# Session_4_HW.net
KiCad netlist of a schematic drawn in EAGLE
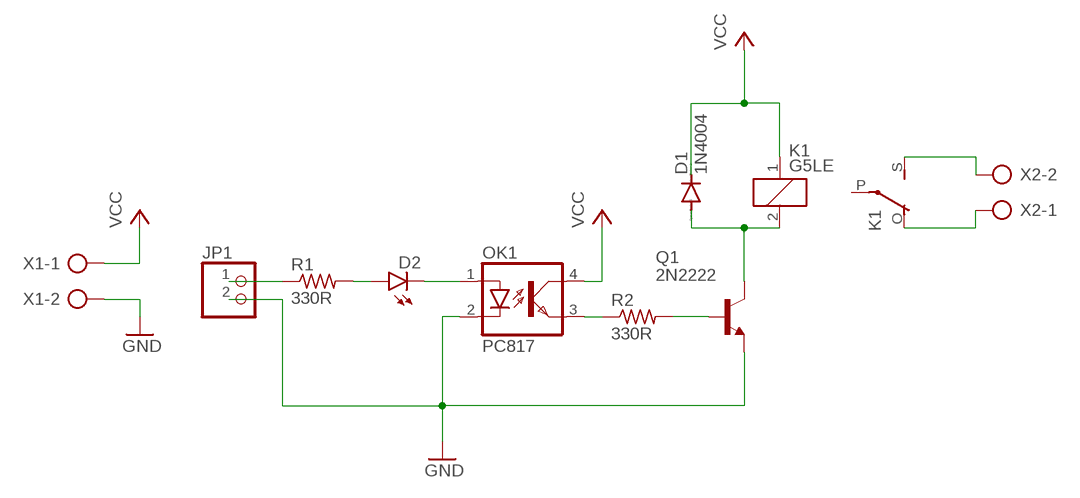
[diagram p0: schematic, sheet 1]

(export (version "E")
  (design (tool "Eeschema 10.0.6"))
  (components
    (comp (ref "D1")
      (value "1N4004")
      (footprint "eagle-import:DO41-10")
      (libsource (lib "eagle-import") (part "1N4004"))
    )
    (comp (ref "D2")
      (value "LED5MM")
      (footprint "eagle-import:LED5MM")
      (libsource (lib "eagle-import") (part "LED5MM"))
    )
    (comp (ref "JP1")
      (value "PINHD-1X2")
      (footprint "eagle-import:1X02")
      (libsource (lib "eagle-import") (part "PINHD-1X2"))
    )
    (comp (ref "K1")
      (value "G5LE")
      (footprint "eagle-import:G5LE")
      (libsource (lib "eagle-import") (part "G5LE"))
    )
    (comp (ref "OK1")
      (value "PC817")
      (footprint "eagle-import:DIL04")
      (fields (field (name "MPN") "PC817X4J000F"))
      (libsource (lib "eagle-import") (part "PC817"))
    )
    (comp (ref "Q1")
      (value "2N2222")
      (footprint "eagle-import:TO18")
      (libsource (lib "eagle-import") (part "2N2222"))
    )
    (comp (ref "R1")
      (value "330R")
      (footprint "eagle-import:0204_7")
      (libsource (lib "eagle-import") (part "R-US_0204/7"))
    )
    (comp (ref "R2")
      (value "330R")
      (footprint "eagle-import:0204_7")
      (libsource (lib "eagle-import") (part "R-US_0204/7"))
    )
    (comp (ref "X1")
      (value "AK500/2")
      (footprint "eagle-import:AK500_2")
      (libsource (lib "eagle-import") (part "AK500/2"))
    )
    (comp (ref "X2")
      (value "AK500/2")
      (footprint "eagle-import:AK500_2")
      (libsource (lib "eagle-import") (part "AK500/2"))
    )
  )
  (nets
    (net (code "1") (name "GND") (class "Default")
      (node (ref "JP1") (pin "2") (pinfunction "2_2") (pintype "passive"))
      (node (ref "OK1") (pin "2") (pinfunction "C_2") (pintype "passive"))
      (node (ref "Q1") (pin "1") (pinfunction "E_1") (pintype "passive"))
      (node (ref "X1") (pin "2") (pinfunction "KL_2") (pintype "passive"))
    )
    (net (code "2") (name "Net-(D2-C)") (class "Default")
      (node (ref "D2") (pin "K") (pinfunction "C_K") (pintype "passive"))
      (node (ref "OK1") (pin "1") (pinfunction "A_1") (pintype "passive"))
    )
    (net (code "3") (name "Net-(D2-PadA)") (class "Default")
      (node (ref "D2") (pin "A") (pinfunction "A_A") (pintype "passive"))
      (node (ref "R1") (pin "2") (pinfunction "2_2") (pintype "passive"))
    )
    (net (code "4") (name "Net-(JP1-Pad1)") (class "Default")
      (node (ref "JP1") (pin "1") (pinfunction "1_1") (pintype "passive"))
      (node (ref "R1") (pin "1") (pinfunction "1_1") (pintype "passive"))
    )
    (net (code "5") (name "Net-(OK1-EMIT)") (class "Default")
      (node (ref "OK1") (pin "3") (pinfunction "EMIT_3") (pintype "passive"))
      (node (ref "R2") (pin "1") (pinfunction "1_1") (pintype "passive"))
    )
    (net (code "6") (name "Net-(Q1-B)") (class "Default")
      (node (ref "Q1") (pin "2") (pinfunction "B_2") (pintype "passive"))
      (node (ref "R2") (pin "2") (pinfunction "2_2") (pintype "passive"))
    )
    (net (code "7") (name "Net-(Q1-C)") (class "Default")
      (node (ref "D1") (pin "A") (pinfunction "A_A") (pintype "passive"))
      (node (ref "K1") (pin "2") (pinfunction "2_2") (pintype "passive"))
      (node (ref "Q1") (pin "3") (pinfunction "C_3") (pintype "passive"))
    )
    (net (code "8") (name "Net-(X2A-KL)") (class "Default")
      (node (ref "K1") (pin "O") (pinfunction "O_O") (pintype "passive"))
      (node (ref "X2") (pin "1") (pinfunction "KL_1") (pintype "passive"))
    )
    (net (code "9") (name "Net-(X2B-KL)") (class "Default")
      (node (ref "K1") (pin "S") (pinfunction "S_S") (pintype "passive"))
      (node (ref "X2") (pin "2") (pinfunction "KL_2") (pintype "passive"))
    )
    (net (code "10") (name "VCC") (class "Default")
      (node (ref "D1") (pin "C") (pinfunction "C_C") (pintype "passive"))
      (node (ref "K1") (pin "1") (pinfunction "1_1") (pintype "passive"))
      (node (ref "OK1") (pin "4") (pinfunction "COL_4") (pintype "passive"))
      (node (ref "X1") (pin "1") (pinfunction "KL_1") (pintype "passive"))
    )
    (net (code "11") (name "unconnected-(K1-PadP)") (class "Default")
      (node (ref "K1") (pin "P") (pinfunction "P_P") (pintype "passive"))
    )
  )
)
